# svis_realsense_d435.net
KiCad netlist of a schematic drawn in EAGLE
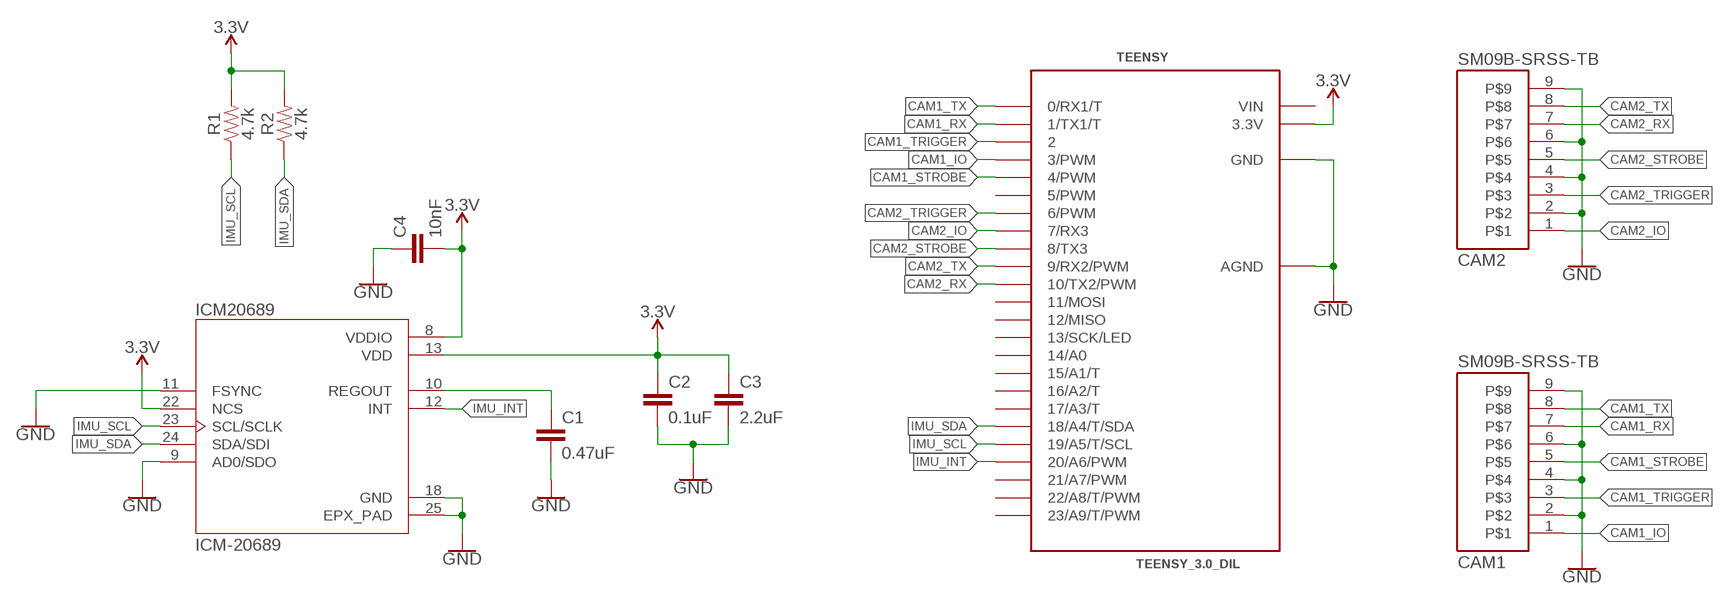
[diagram p0: schematic, sheet 1]

(export (version "E")
  (design (tool "Eeschema 10.0.6"))
  (components
    (comp (ref "C1")
      (value "0.47uF")
      (footprint "eagle-import:0603")
      (libsource (lib "eagle-import") (part "0.1UF-0603-25V-(+80/-20%)"))
    )
    (comp (ref "C2")
      (value "0.1uF")
      (footprint "eagle-import:0603")
      (libsource (lib "eagle-import") (part "0.1UF-0603-25V-(+80/-20%)"))
    )
    (comp (ref "C3")
      (value "2.2uF")
      (footprint "eagle-import:0603")
      (libsource (lib "eagle-import") (part "2.2UF-0603-10V-20%"))
    )
    (comp (ref "C4")
      (value "10nF")
      (footprint "eagle-import:0603")
      (libsource (lib "eagle-import") (part "0.1UF-0603-25V-(+80/-20%)"))
    )
    (comp (ref "CAM1")
      (value "SM09B-SRSS-TB")
      (footprint "eagle-import:SM09B-SRSS-TB")
      (libsource (lib "eagle-import") (part "SM09B-SRSS-TB"))
    )
    (comp (ref "CAM2")
      (value "SM09B-SRSS-TB")
      (footprint "eagle-import:SM09B-SRSS-TB")
      (libsource (lib "eagle-import") (part "SM09B-SRSS-TB"))
    )
    (comp (ref "ICM20689")
      (value "ICM-20689")
      (footprint "eagle-import:QFN50P400X400X95-25N")
      (fields (field (name "MF") "TDK-InvenSense"))
      (libsource (lib "eagle-import") (part "ICM-20689"))
    )
    (comp (ref "R1")
      (value "4.7k")
      (footprint "eagle-import:0603")
      (libsource (lib "eagle-import") (part "4.7KOHM-0603-1/10W-1%"))
    )
    (comp (ref "R2")
      (value "4.7k")
      (footprint "eagle-import:0603")
      (libsource (lib "eagle-import") (part "4.7KOHM-0603-1/10W-1%"))
    )
    (comp (ref "TEENSY")
      (value "TEENSY_3.0_DIL")
      (footprint "eagle-import:TEENSY_3.0-3.2&LC_DIL")
      (libsource (lib "eagle-import") (part "TEENSY_3.0_DIL"))
    )
  )
  (nets
    (net (code "1") (name "/VIN") (class "Default")
      (node (ref "TEENSY") (pin "VIN") (pinfunction "VIN_VIN") (pintype "power_in"))
    )
    (net (code "2") (name "3.3V") (class "Default")
      (node (ref "C2") (pin "1") (pinfunction "1_1") (pintype "passive"))
      (node (ref "C3") (pin "1") (pinfunction "1_1") (pintype "passive"))
      (node (ref "C4") (pin "2") (pinfunction "2_2") (pintype "passive"))
      (node (ref "ICM20689") (pin "13") (pinfunction "VDD_13") (pintype "power_in"))
      (node (ref "ICM20689") (pin "22") (pinfunction "NCS_22") (pintype "input"))
      (node (ref "ICM20689") (pin "8") (pinfunction "VDDIO_8") (pintype "power_in"))
      (node (ref "R1") (pin "2") (pinfunction "2_2") (pintype "passive"))
      (node (ref "R2") (pin "2") (pinfunction "2_2") (pintype "passive"))
      (node (ref "TEENSY") (pin "3.3V") (pinfunction "3.3V_3.3V") (pintype "power_in"))
    )
    (net (code "3") (name "CAM1_IO") (class "Default")
      (node (ref "CAM1") (pin "1") (pinfunction "P$1_1") (pintype "bidirectional"))
      (node (ref "TEENSY") (pin "3") (pinfunction "3/PWM_3") (pintype "bidirectional"))
    )
    (net (code "4") (name "CAM1_RX") (class "Default")
      (node (ref "CAM1") (pin "7") (pinfunction "P$7_7") (pintype "bidirectional"))
      (node (ref "TEENSY") (pin "1") (pinfunction "1/TX1/T_1") (pintype "bidirectional"))
    )
    (net (code "5") (name "CAM1_STROBE") (class "Default")
      (node (ref "CAM1") (pin "5") (pinfunction "P$5_5") (pintype "bidirectional"))
      (node (ref "TEENSY") (pin "4") (pinfunction "4/PWM_4") (pintype "bidirectional"))
    )
    (net (code "6") (name "CAM1_TRIGGER") (class "Default")
      (node (ref "CAM1") (pin "3") (pinfunction "P$3_3") (pintype "bidirectional"))
      (node (ref "TEENSY") (pin "2") (pinfunction "2_2") (pintype "bidirectional"))
    )
    (net (code "7") (name "CAM1_TX") (class "Default")
      (node (ref "CAM1") (pin "8") (pinfunction "P$8_8") (pintype "bidirectional"))
      (node (ref "TEENSY") (pin "0") (pinfunction "0/RX1/T_0") (pintype "bidirectional"))
    )
    (net (code "8") (name "CAM2_IO") (class "Default")
      (node (ref "CAM2") (pin "1") (pinfunction "P$1_1") (pintype "bidirectional"))
      (node (ref "TEENSY") (pin "7") (pinfunction "7/RX3_7") (pintype "bidirectional"))
    )
    (net (code "9") (name "CAM2_RX") (class "Default")
      (node (ref "CAM2") (pin "7") (pinfunction "P$7_7") (pintype "bidirectional"))
      (node (ref "TEENSY") (pin "10") (pinfunction "10/TX2/PWM_10") (pintype "bidirectional"))
    )
    (net (code "10") (name "CAM2_STROBE") (class "Default")
      (node (ref "CAM2") (pin "5") (pinfunction "P$5_5") (pintype "bidirectional"))
      (node (ref "TEENSY") (pin "8") (pinfunction "8/TX3_8") (pintype "bidirectional"))
    )
    (net (code "11") (name "CAM2_TRIGGER") (class "Default")
      (node (ref "CAM2") (pin "3") (pinfunction "P$3_3") (pintype "bidirectional"))
      (node (ref "TEENSY") (pin "6") (pinfunction "6/PWM_6") (pintype "bidirectional"))
    )
    (net (code "12") (name "CAM2_TX") (class "Default")
      (node (ref "CAM2") (pin "8") (pinfunction "P$8_8") (pintype "bidirectional"))
      (node (ref "TEENSY") (pin "9") (pinfunction "9/RX2/PWM_9") (pintype "bidirectional"))
    )
    (net (code "13") (name "GND") (class "Default")
      (node (ref "C1") (pin "2") (pinfunction "2_2") (pintype "passive"))
      (node (ref "C2") (pin "2") (pinfunction "2_2") (pintype "passive"))
      (node (ref "C3") (pin "2") (pinfunction "2_2") (pintype "passive"))
      (node (ref "C4") (pin "1") (pinfunction "1_1") (pintype "passive"))
      (node (ref "CAM1") (pin "2") (pinfunction "P$2_2") (pintype "bidirectional"))
      (node (ref "CAM1") (pin "4") (pinfunction "P$4_4") (pintype "bidirectional"))
      (node (ref "CAM1") (pin "6") (pinfunction "P$6_6") (pintype "bidirectional"))
      (node (ref "CAM1") (pin "9") (pinfunction "P$9_9") (pintype "bidirectional"))
      (node (ref "CAM2") (pin "2") (pinfunction "P$2_2") (pintype "bidirectional"))
      (node (ref "CAM2") (pin "4") (pinfunction "P$4_4") (pintype "bidirectional"))
      (node (ref "CAM2") (pin "6") (pinfunction "P$6_6") (pintype "bidirectional"))
      (node (ref "CAM2") (pin "9") (pinfunction "P$9_9") (pintype "bidirectional"))
      (node (ref "ICM20689") (pin "11") (pinfunction "FSYNC_11") (pintype "input"))
      (node (ref "ICM20689") (pin "18") (pinfunction "GND_18") (pintype "power_in"))
      (node (ref "ICM20689") (pin "25") (pinfunction "EPX_PAD_25") (pintype "power_in"))
      (node (ref "ICM20689") (pin "9") (pinfunction "AD0/SDO_9") (pintype "bidirectional"))
      (node (ref "TEENSY") (pin "AGND") (pinfunction "AGND_AGND") (pintype "power_in"))
      (node (ref "TEENSY") (pin "GND") (pinfunction "GND_GND") (pintype "power_in"))
    )
    (net (code "14") (name "IMU_INT") (class "Default")
      (node (ref "ICM20689") (pin "12") (pinfunction "INT_12") (pintype "output"))
      (node (ref "TEENSY") (pin "20/A6") (pinfunction "20/A6/PWM_20/A6") (pintype "bidirectional"))
    )
    (net (code "15") (name "IMU_SCL") (class "Default")
      (node (ref "ICM20689") (pin "23") (pinfunction "SCL/SCLK_23") (pintype "input"))
      (node (ref "R1") (pin "1") (pinfunction "1_1") (pintype "passive"))
      (node (ref "TEENSY") (pin "19/A5") (pinfunction "19/A5/T/SCL_19/A5") (pintype "bidirectional"))
    )
    (net (code "16") (name "IMU_SDA") (class "Default")
      (node (ref "ICM20689") (pin "24") (pinfunction "SDA/SDI_24") (pintype "bidirectional"))
      (node (ref "R2") (pin "1") (pinfunction "1_1") (pintype "passive"))
      (node (ref "TEENSY") (pin "18/A4") (pinfunction "18/A4/T/SDA_18/A4") (pintype "bidirectional"))
    )
    (net (code "17") (name "Net-(ICM20689-REGOUT)") (class "Default")
      (node (ref "C1") (pin "1") (pinfunction "1_1") (pintype "passive"))
      (node (ref "ICM20689") (pin "10") (pinfunction "REGOUT_10") (pintype "output"))
    )
    (net (code "18") (name "unconnected-(TEENSY-5{slash}PWM-Pad5)") (class "Default")
      (node (ref "TEENSY") (pin "5") (pinfunction "5/PWM_5") (pintype "bidirectional"))
    )
    (net (code "19") (name "unconnected-(TEENSY-11{slash}MOSI-Pad11)") (class "Default")
      (node (ref "TEENSY") (pin "11") (pinfunction "11/MOSI_11") (pintype "bidirectional"))
    )
    (net (code "20") (name "unconnected-(TEENSY-12{slash}MISO-Pad12)") (class "Default")
      (node (ref "TEENSY") (pin "12") (pinfunction "12/MISO_12") (pintype "bidirectional"))
    )
    (net (code "21") (name "unconnected-(TEENSY-13{slash}SCK{slash}LED-Pad13)") (class "Default")
      (node (ref "TEENSY") (pin "13") (pinfunction "13/SCK/LED_13") (pintype "bidirectional"))
    )
    (net (code "22") (name "unconnected-(TEENSY-15{slash}A1{slash}T-Pad15{slash}A1)") (class "Default")
      (node (ref "TEENSY") (pin "15/A1") (pinfunction "15/A1/T_15/A1") (pintype "bidirectional"))
    )
    (net (code "23") (name "unconnected-(TEENSY-16{slash}A2{slash}T-Pad16{slash}A2)") (class "Default")
      (node (ref "TEENSY") (pin "16/A2") (pinfunction "16/A2/T_16/A2") (pintype "bidirectional"))
    )
    (net (code "24") (name "unconnected-(TEENSY-17{slash}A3{slash}T-Pad17{slash}A3)") (class "Default")
      (node (ref "TEENSY") (pin "17/A3") (pinfunction "17/A3/T_17/A3") (pintype "bidirectional"))
    )
    (net (code "25") (name "unconnected-(TEENSY-21{slash}A7{slash}PWM-Pad21{slash}A7)") (class "Default")
      (node (ref "TEENSY") (pin "21/A7") (pinfunction "21/A7/PWM_21/A7") (pintype "bidirectional"))
    )
    (net (code "26") (name "unconnected-(TEENSY-22{slash}A8{slash}T{slash}PWM-Pad22{slash}A8)") (class "Default")
      (node (ref "TEENSY") (pin "22/A8") (pinfunction "22/A8/T/PWM_22/A8") (pintype "bidirectional"))
    )
    (net (code "27") (name "unconnected-(TEENSY-23{slash}A9{slash}T{slash}PWM-Pad23{slash}A9)") (class "Default")
      (node (ref "TEENSY") (pin "23/A9") (pinfunction "23/A9/T/PWM_23/A9") (pintype "bidirectional"))
    )
    (net (code "28") (name "unconnected-(TEENSY-Pad14{slash}A0)") (class "Default")
      (node (ref "TEENSY") (pin "14/A0") (pinfunction "14/A0_14/A0") (pintype "bidirectional"))
    )
  )
)
